# DataVideoPort.net
KiCad netlist of a schematic drawn in Altium Designer
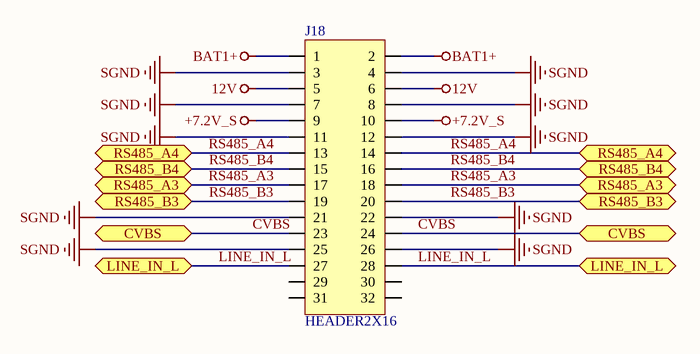
[diagram p0: DataVideoPort.SchDoc]

(export (version "E")
  (design (tool "Eeschema 10.0.6"))
  (components
    (comp (ref "J18")
      (value "HEADER2X16")
      (footprint "HD2X16-2.00")
      (libsource (lib "Connector Class") (part "HEADER2X16"))
    )
  )
  (nets
    (net (code "1") (name "+7.2V_S") (class "Default")
      (node (ref "J18") (pin "10") (pinfunction "10_10") (pintype "passive"))
      (node (ref "J18") (pin "9") (pinfunction "9_9") (pintype "passive"))
    )
    (net (code "2") (name "/CVBS") (class "Default")
      (node (ref "J18") (pin "23") (pinfunction "23_23") (pintype "passive"))
      (node (ref "J18") (pin "24") (pinfunction "24_24") (pintype "passive"))
    )
    (net (code "3") (name "/LINE_IN_L") (class "Default")
      (node (ref "J18") (pin "27") (pinfunction "27_27") (pintype "passive"))
      (node (ref "J18") (pin "28") (pinfunction "28_28") (pintype "passive"))
    )
    (net (code "4") (name "/RS485_A3") (class "Default")
      (node (ref "J18") (pin "17") (pinfunction "17_17") (pintype "passive"))
      (node (ref "J18") (pin "18") (pinfunction "18_18") (pintype "passive"))
    )
    (net (code "5") (name "/RS485_A4") (class "Default")
      (node (ref "J18") (pin "13") (pinfunction "13_13") (pintype "passive"))
      (node (ref "J18") (pin "14") (pinfunction "14_14") (pintype "passive"))
    )
    (net (code "6") (name "/RS485_B3") (class "Default")
      (node (ref "J18") (pin "19") (pinfunction "19_19") (pintype "passive"))
      (node (ref "J18") (pin "20") (pinfunction "20_20") (pintype "passive"))
    )
    (net (code "7") (name "/RS485_B4") (class "Default")
      (node (ref "J18") (pin "15") (pinfunction "15_15") (pintype "passive"))
      (node (ref "J18") (pin "16") (pinfunction "16_16") (pintype "passive"))
    )
    (net (code "8") (name "12V") (class "Default")
      (node (ref "J18") (pin "5") (pinfunction "5_5") (pintype "passive"))
      (node (ref "J18") (pin "6") (pinfunction "6_6") (pintype "passive"))
    )
    (net (code "9") (name "BAT1+") (class "Default")
      (node (ref "J18") (pin "1") (pinfunction "1_1") (pintype "passive"))
      (node (ref "J18") (pin "2") (pinfunction "2_2") (pintype "passive"))
    )
    (net (code "10") (name "SGND") (class "Default")
      (node (ref "J18") (pin "11") (pinfunction "11_11") (pintype "passive"))
      (node (ref "J18") (pin "12") (pinfunction "12_12") (pintype "passive"))
      (node (ref "J18") (pin "21") (pinfunction "21_21") (pintype "passive"))
      (node (ref "J18") (pin "22") (pinfunction "22_22") (pintype "passive"))
      (node (ref "J18") (pin "25") (pinfunction "25_25") (pintype "passive"))
      (node (ref "J18") (pin "26") (pinfunction "26_26") (pintype "passive"))
      (node (ref "J18") (pin "3") (pinfunction "3_3") (pintype "passive"))
      (node (ref "J18") (pin "4") (pinfunction "4_4") (pintype "passive"))
      (node (ref "J18") (pin "7") (pinfunction "7_7") (pintype "passive"))
      (node (ref "J18") (pin "8") (pinfunction "8_8") (pintype "passive"))
    )
    (net (code "11") (name "unconnected-(J18-Pad29)") (class "Default")
      (node (ref "J18") (pin "29") (pinfunction "29_29") (pintype "passive"))
    )
    (net (code "12") (name "unconnected-(J18-Pad30)") (class "Default")
      (node (ref "J18") (pin "30") (pinfunction "30_30") (pintype "passive"))
    )
    (net (code "13") (name "unconnected-(J18-Pad31)") (class "Default")
      (node (ref "J18") (pin "31") (pinfunction "31_31") (pintype "passive"))
    )
    (net (code "14") (name "unconnected-(J18-Pad32)") (class "Default")
      (node (ref "J18") (pin "32") (pinfunction "32_32") (pintype "passive"))
    )
  )
)
